# Sheet1.net
KiCad netlist of a schematic drawn in Altium Designer
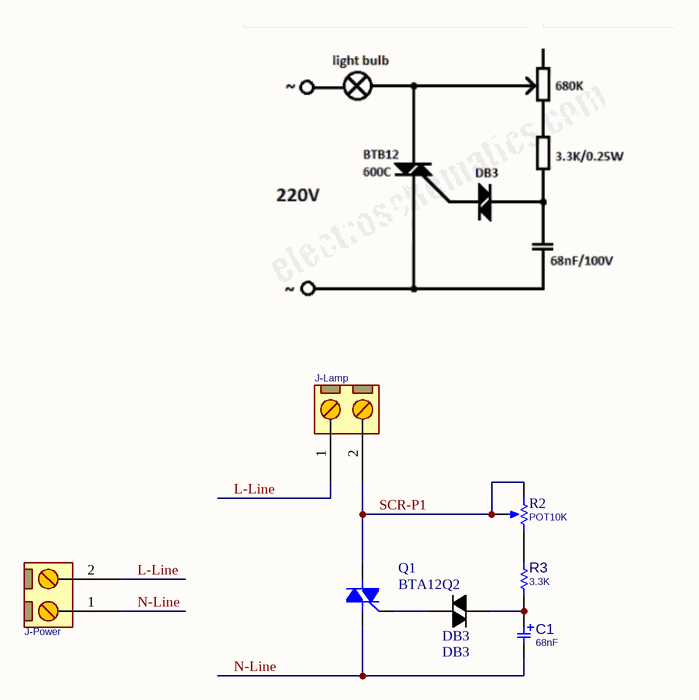
[diagram p0: Sheet1.SchDoc]

(export (version "E")
  (design (tool "Eeschema 10.0.6"))
  (components
    (comp (ref "C1")
      (value "68nF")
      (footprint "C_FLM_7X5H11")
      (description "CAP, THD, FILM,")
      (fields (field (name "MANF_P#") "MANF_PART#") (field (name "MANF") "MANF"))
      (libsource (lib "passive_thd") (part "CAP_THD_FLM"))
    )
    (comp (ref "J-Lamp")
      (value "CONN_TB2")
      (footprint "MSTB_2")
      (description "CONN, PHOENIX MSTB, 5-G, 5.08mm pitch")
      (libsource (lib "conn_power_terminalB") (part "CONN_MSTB_2"))
    )
    (comp (ref "J-Power")
      (value "CONN_TB2")
      (footprint "MSTB_2")
      (description "CONN, PHOENIX MSTB, 5-G, 5.08mm pitch")
      (libsource (lib "") (part "CONN_MSTB_2_1"))
    )
    (comp (ref "Q1")
      (value "BTA12")
      (footprint "TO220_3")
      (description "Triac, 600V, 12A, TO-220")
      (fields (field (name "MANF_P#") "BTA12-600BW, BTA12-600CW, BTA12-600TW") (field (name "MANF") "ST"))
      (libsource (lib "triac_diac") (part "TRIAC_BTA12-600_TO220"))
    )
    (comp (ref "Q2")
      (value "DB3")
      (footprint "D_AX03_DO35")
      (description "Diac, 32VBO, DO-35")
      (fields (field (name "MANF") "ST") (field (name "ALTIUM_VALUE") "DB3"))
      (libsource (lib "triac_diac") (part "DIAC_DB3_DO35"))
    )
    (comp (ref "R2")
      (value "POT10K")
      (footprint "VOL_R")
      (description "RESISTOR, THD, Potentiometer Volume")
      (libsource (lib "resistor_pot_trimmer") (part "RES_THD_POT_VOL"))
    )
    (comp (ref "R3")
      (value "3.3K")
      (footprint "R025W_AX04")
      (description "RESISTOR, THD")
      (fields (field (name "MANF_P#") "RK73H1ETTP4701F") (field (name "MANF") "KOA SPEER"))
      (libsource (lib "passive_thd") (part "RES_THD"))
    )
  )
  (nets
    (net (code "1") (name "/L-Line") (class "Default")
      (node (ref "J-Lamp") (pin "1") (pinfunction "1_1") (pintype "passive"))
      (node (ref "J-Power") (pin "2") (pinfunction "2_2") (pintype "passive"))
    )
    (net (code "2") (name "/N-Line") (class "Default")
      (node (ref "C1") (pin "2") (pinfunction "2_2") (pintype "passive"))
      (node (ref "J-Power") (pin "1") (pinfunction "1_1") (pintype "passive"))
      (node (ref "Q1") (pin "1") (pinfunction "T1_1") (pintype "passive"))
    )
    (net (code "3") (name "/SCR-P1") (class "Default")
      (node (ref "J-Lamp") (pin "2") (pinfunction "2_2") (pintype "passive"))
      (node (ref "Q1") (pin "2") (pinfunction "T2_2") (pintype "passive"))
      (node (ref "R2") (pin "1") (pinfunction "TOP_1") (pintype "passive"))
      (node (ref "R2") (pin "2") (pinfunction "TAP_2") (pintype "passive"))
    )
    (net (code "4") (name "Net-(Q1-G)") (class "Default")
      (node (ref "Q1") (pin "3") (pinfunction "G_3") (pintype "passive"))
      (node (ref "Q2") (pin "1") (pinfunction "A1_1") (pintype "passive"))
    )
    (net (code "5") (name "Net-(Q2-A2)") (class "Default")
      (node (ref "C1") (pin "1") (pinfunction "1_1") (pintype "passive"))
      (node (ref "Q2") (pin "2") (pinfunction "A2_2") (pintype "passive"))
      (node (ref "R3") (pin "1") (pinfunction "1_1") (pintype "passive"))
    )
    (net (code "6") (name "Net-(R2-BOT)") (class "Default")
      (node (ref "R2") (pin "3") (pinfunction "BOT_3") (pintype "passive"))
      (node (ref "R3") (pin "2") (pinfunction "2_2") (pintype "passive"))
    )
  )
)
